# 4-port.net
KiCad netlist of a schematic drawn in EAGLE
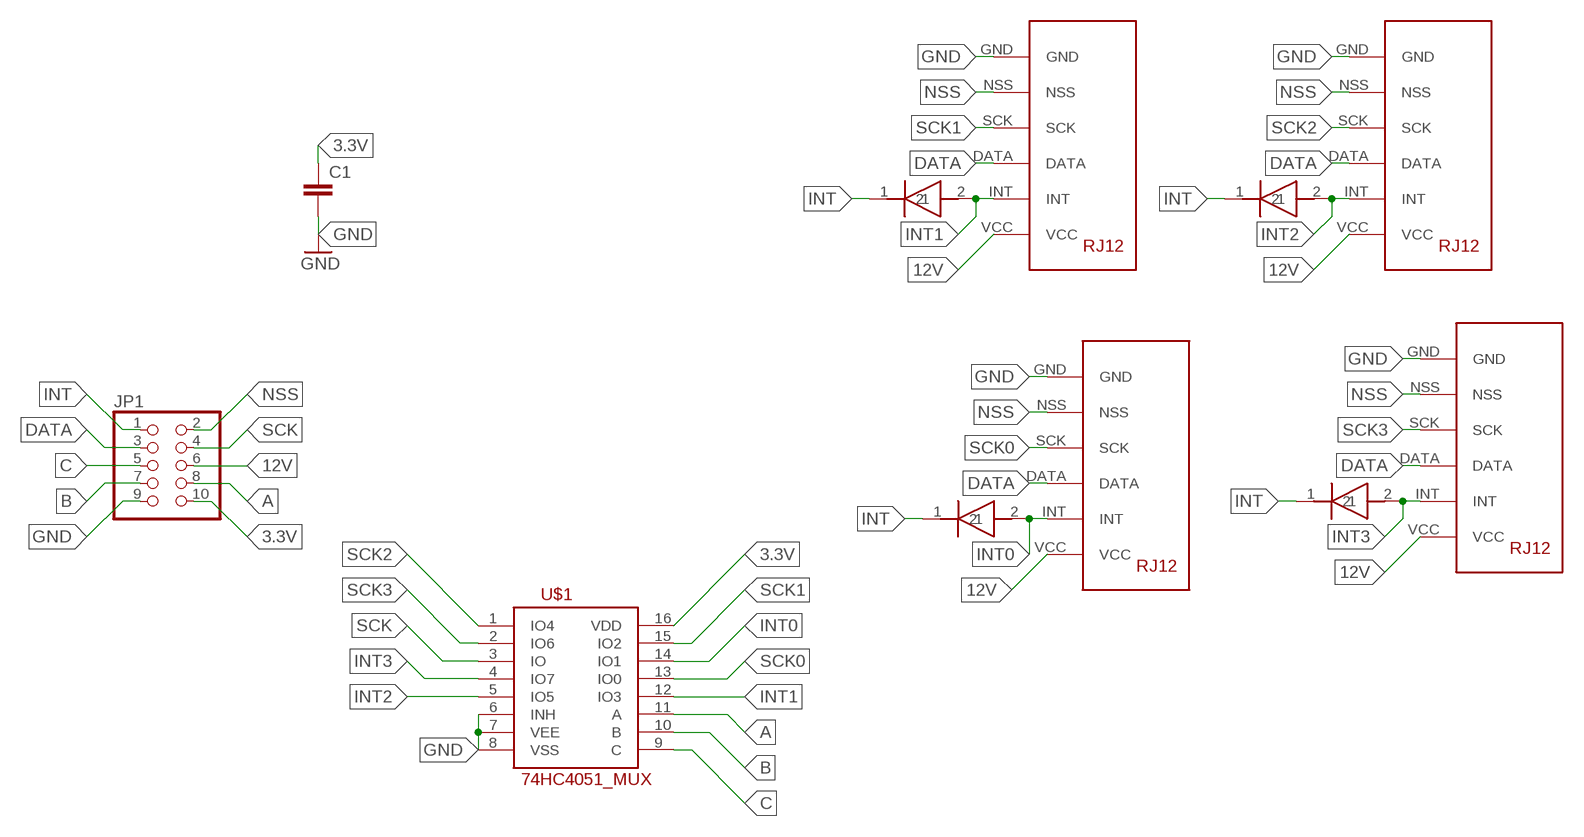
[diagram p0: schematic, sheet 1]

(export (version "E")
  (design (tool "Eeschema 10.0.6"))
  (components
    (comp (ref "C1")
      (value "C-EUC1206")
      (footprint "eagle-import:C1206")
      (libsource (lib "eagle-import") (part "C-EUC1206"))
    )
    (comp (ref "JP1")
      (value "PINHD-2X5")
      (footprint "eagle-import:2X05")
      (libsource (lib "eagle-import") (part "PINHD-2X5"))
    )
    (comp (ref "U$1")
      (value "74HC4051_MUX")
      (footprint "eagle-import:SO16")
      (libsource (lib "eagle-import") (part "74HC4051_MUX"))
    )
    (comp (ref "U$2")
      (value "RJ12SMD")
      (footprint "eagle-import:RJ12_SMD")
      (libsource (lib "eagle-import") (part "RJ12SMD"))
    )
    (comp (ref "U$3")
      (value "DIODE")
      (footprint "eagle-import:DIL_DIODE_SMD")
      (libsource (lib "eagle-import") (part "DIODE"))
    )
    (comp (ref "U$4")
      (value "RJ12SMD")
      (footprint "eagle-import:RJ12_SMD")
      (libsource (lib "eagle-import") (part "RJ12SMD"))
    )
    (comp (ref "U$5")
      (value "RJ12SMD")
      (footprint "eagle-import:RJ12_SMD")
      (libsource (lib "eagle-import") (part "RJ12SMD"))
    )
    (comp (ref "U$6")
      (value "DIODE")
      (footprint "eagle-import:DIL_DIODE_SMD")
      (libsource (lib "eagle-import") (part "DIODE"))
    )
    (comp (ref "U$7")
      (value "RJ12SMD")
      (footprint "eagle-import:RJ12_SMD")
      (libsource (lib "eagle-import") (part "RJ12SMD"))
    )
    (comp (ref "U$8")
      (value "DIODE")
      (footprint "eagle-import:DIL_DIODE_SMD")
      (libsource (lib "eagle-import") (part "DIODE"))
    )
    (comp (ref "U$9")
      (value "DIODE")
      (footprint "eagle-import:DIL_DIODE_SMD")
      (libsource (lib "eagle-import") (part "DIODE"))
    )
  )
  (nets
    (net (code "1") (name "3.3V") (class "Default")
      (node (ref "C1") (pin "1") (pinfunction "1_1") (pintype "passive"))
      (node (ref "JP1") (pin "10") (pinfunction "10_10") (pintype "passive"))
      (node (ref "U$1") (pin "16") (pinfunction "VDD_16") (pintype "bidirectional"))
    )
    (net (code "2") (name "12V") (class "Default")
      (node (ref "JP1") (pin "6") (pinfunction "6_6") (pintype "passive"))
      (node (ref "U$2") (pin "VCC") (pinfunction "VCC_VCC") (pintype "bidirectional"))
      (node (ref "U$4") (pin "VCC") (pinfunction "VCC_VCC") (pintype "bidirectional"))
      (node (ref "U$5") (pin "VCC") (pinfunction "VCC_VCC") (pintype "bidirectional"))
      (node (ref "U$7") (pin "VCC") (pinfunction "VCC_VCC") (pintype "bidirectional"))
    )
    (net (code "3") (name "A") (class "Default")
      (node (ref "JP1") (pin "8") (pinfunction "8_8") (pintype "passive"))
      (node (ref "U$1") (pin "11") (pinfunction "A_11") (pintype "bidirectional"))
    )
    (net (code "4") (name "B") (class "Default")
      (node (ref "JP1") (pin "7") (pinfunction "7_7") (pintype "passive"))
      (node (ref "U$1") (pin "10") (pinfunction "B_10") (pintype "bidirectional"))
    )
    (net (code "5") (name "C") (class "Default")
      (node (ref "JP1") (pin "5") (pinfunction "5_5") (pintype "passive"))
      (node (ref "U$1") (pin "9") (pinfunction "C_9") (pintype "bidirectional"))
    )
    (net (code "6") (name "DATA") (class "Default")
      (node (ref "JP1") (pin "3") (pinfunction "3_3") (pintype "passive"))
      (node (ref "U$2") (pin "DATA") (pinfunction "DATA_DATA") (pintype "bidirectional"))
      (node (ref "U$4") (pin "DATA") (pinfunction "DATA_DATA") (pintype "bidirectional"))
      (node (ref "U$5") (pin "DATA") (pinfunction "DATA_DATA") (pintype "bidirectional"))
      (node (ref "U$7") (pin "DATA") (pinfunction "DATA_DATA") (pintype "bidirectional"))
    )
    (net (code "7") (name "GND") (class "Default")
      (node (ref "C1") (pin "2") (pinfunction "2_2") (pintype "passive"))
      (node (ref "JP1") (pin "9") (pinfunction "9_9") (pintype "passive"))
      (node (ref "U$1") (pin "6") (pinfunction "INH_6") (pintype "bidirectional"))
      (node (ref "U$1") (pin "7") (pinfunction "VEE_7") (pintype "bidirectional"))
      (node (ref "U$1") (pin "8") (pinfunction "VSS_8") (pintype "bidirectional"))
      (node (ref "U$2") (pin "GND") (pinfunction "GND_GND") (pintype "bidirectional"))
      (node (ref "U$4") (pin "GND") (pinfunction "GND_GND") (pintype "bidirectional"))
      (node (ref "U$5") (pin "GND") (pinfunction "GND_GND") (pintype "bidirectional"))
      (node (ref "U$7") (pin "GND") (pinfunction "GND_GND") (pintype "bidirectional"))
    )
    (net (code "8") (name "INT") (class "Default")
      (node (ref "JP1") (pin "1") (pinfunction "1_1") (pintype "passive"))
      (node (ref "U$3") (pin "1") (pinfunction "1_1") (pintype "bidirectional"))
      (node (ref "U$6") (pin "1") (pinfunction "1_1") (pintype "bidirectional"))
      (node (ref "U$8") (pin "1") (pinfunction "1_1") (pintype "bidirectional"))
      (node (ref "U$9") (pin "1") (pinfunction "1_1") (pintype "bidirectional"))
    )
    (net (code "9") (name "INT0") (class "Default")
      (node (ref "U$1") (pin "14") (pinfunction "IO1_14") (pintype "bidirectional"))
      (node (ref "U$2") (pin "INT") (pinfunction "INT_INT") (pintype "bidirectional"))
      (node (ref "U$3") (pin "2") (pinfunction "2_2") (pintype "bidirectional"))
    )
    (net (code "10") (name "INT1") (class "Default")
      (node (ref "U$1") (pin "12") (pinfunction "IO3_12") (pintype "bidirectional"))
      (node (ref "U$4") (pin "INT") (pinfunction "INT_INT") (pintype "bidirectional"))
      (node (ref "U$9") (pin "2") (pinfunction "2_2") (pintype "bidirectional"))
    )
    (net (code "11") (name "INT2") (class "Default")
      (node (ref "U$1") (pin "5") (pinfunction "IO5_5") (pintype "bidirectional"))
      (node (ref "U$5") (pin "INT") (pinfunction "INT_INT") (pintype "bidirectional"))
      (node (ref "U$6") (pin "2") (pinfunction "2_2") (pintype "bidirectional"))
    )
    (net (code "12") (name "INT3") (class "Default")
      (node (ref "U$1") (pin "4") (pinfunction "IO7_4") (pintype "bidirectional"))
      (node (ref "U$7") (pin "INT") (pinfunction "INT_INT") (pintype "bidirectional"))
      (node (ref "U$8") (pin "2") (pinfunction "2_2") (pintype "bidirectional"))
    )
    (net (code "13") (name "NSS") (class "Default")
      (node (ref "JP1") (pin "2") (pinfunction "2_2") (pintype "passive"))
      (node (ref "U$2") (pin "NSS") (pinfunction "NSS_NSS") (pintype "bidirectional"))
      (node (ref "U$4") (pin "NSS") (pinfunction "NSS_NSS") (pintype "bidirectional"))
      (node (ref "U$5") (pin "NSS") (pinfunction "NSS_NSS") (pintype "bidirectional"))
      (node (ref "U$7") (pin "NSS") (pinfunction "NSS_NSS") (pintype "bidirectional"))
    )
    (net (code "14") (name "SCK") (class "Default")
      (node (ref "JP1") (pin "4") (pinfunction "4_4") (pintype "passive"))
      (node (ref "U$1") (pin "3") (pinfunction "IO_3") (pintype "bidirectional"))
    )
    (net (code "15") (name "SCK0") (class "Default")
      (node (ref "U$1") (pin "13") (pinfunction "IO0_13") (pintype "bidirectional"))
      (node (ref "U$2") (pin "SCK") (pinfunction "SCK_SCK") (pintype "bidirectional"))
    )
    (net (code "16") (name "SCK1") (class "Default")
      (node (ref "U$1") (pin "15") (pinfunction "IO2_15") (pintype "bidirectional"))
      (node (ref "U$4") (pin "SCK") (pinfunction "SCK_SCK") (pintype "bidirectional"))
    )
    (net (code "17") (name "SCK2") (class "Default")
      (node (ref "U$1") (pin "1") (pinfunction "IO4_1") (pintype "bidirectional"))
      (node (ref "U$5") (pin "SCK") (pinfunction "SCK_SCK") (pintype "bidirectional"))
    )
    (net (code "18") (name "SCK3") (class "Default")
      (node (ref "U$1") (pin "2") (pinfunction "IO6_2") (pintype "bidirectional"))
      (node (ref "U$7") (pin "SCK") (pinfunction "SCK_SCK") (pintype "bidirectional"))
    )
  )
)
